# FEV-60_Motor_Driver_OnePhase.net
KiCad netlist of a schematic drawn in Altium Designer
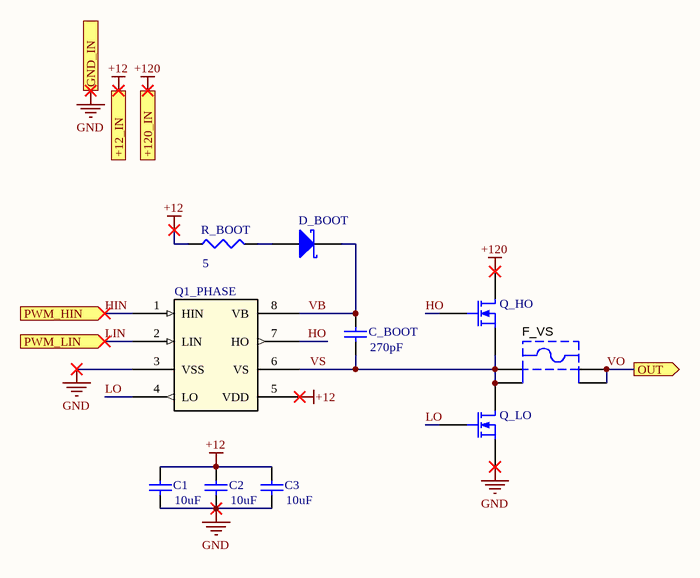
[diagram p0: FEV-60_Motor_Driver_OnePhase.SchDoc]

(export (version "E")
  (design (tool "Eeschema 10.0.6"))
  (components
    (comp (ref "C1")
      (value "10uF")
      (footprint "1608[0603]")
      (description "Capacitor (Semiconductor SIM Model)")
      (fields (field (name "Comment") "Cap Semi") (field (name "PUBLISHER") "Altium Limited"))
      (libsource (lib "Miscellaneous Devices") (part "Cap Semi"))
    )
    (comp (ref "C2")
      (value "10uF")
      (footprint "1608[0603]")
      (description "Capacitor (Semiconductor SIM Model)")
      (fields (field (name "Comment") "Cap Semi") (field (name "PUBLISHER") "Altium Limited"))
      (libsource (lib "Miscellaneous Devices") (part "Cap Semi"))
    )
    (comp (ref "C3")
      (value "10uF")
      (footprint "1608[0603]")
      (description "Capacitor (Semiconductor SIM Model)")
      (fields (field (name "Comment") "Cap Semi") (field (name "PUBLISHER") "Altium Limited"))
      (libsource (lib "Miscellaneous Devices") (part "Cap Semi"))
    )
    (comp (ref "C_BOOT")
      (value "270pF")
      (footprint "1608[0603]")
      (description "Capacitor (Semiconductor SIM Model)")
      (fields (field (name "Comment") "Cap Semi") (field (name "PUBLISHER") "Altium Limited"))
      (libsource (lib "Miscellaneous Devices") (part "Cap Semi"))
    )
    (comp (ref "D_BOOT")
      (value "STPS2200U")
      (footprint "SMB")
      (description "Schottky Diode")
      (fields (field (name "PUBLISHER") "Altium Limited"))
      (libsource (lib "Miscellaneous Devices") (part "D Schottky"))
    )
    (comp (ref "F_VS")
      (value "3568")
      (footprint "KSTN-3568_V")
      (description "Fuse Holder, 20 A, 500 V, -50 to 145 degC, 4-Pin THD, RoHS")
      (fields (field (name "MANUFACTURER") "Keystone"))
      (libsource (lib "FEV-60_Lib") (part "CMP-2000-05464-1"))
    )
    (comp (ref "Q1_PHASE")
      (value "FAN7191-F085")
      (footprint "SOIC8")
      (description "600 V / 4.5 A, High and Low\r\nSide Automotive Gate\r\nDriver IC")
      (fields (field (name "MANUFACTURER") "On Semiconductor"))
      (libsource (lib "FEV-60_Lib") (part "FAN7191-F085"))
    )
    (comp (ref "Q_HO")
      (value "TPH2900ENH")
      (footprint "TPH2900ENH")
      (description "N-Channel 200V 33A (Ta) 78W (Tc) Surface Mount 8-SOP Advance (5x5)")
      (fields (field (name "MANUFACTURER") "Toshiba") (field (name "PART NUMBER") "TPH2900ENHL1QCT-ND"))
      (libsource (lib "FEV-60_Lib") (part "TPH2900ENH"))
    )
    (comp (ref "Q_LO")
      (value "TPH2900ENH")
      (footprint "TPH2900ENH")
      (description "N-Channel 200V 33A (Ta) 78W (Tc) Surface Mount 8-SOP Advance (5x5)")
      (fields (field (name "MANUFACTURER") "Toshiba") (field (name "PART NUMBER") "TPH2900ENHL1QCT-ND"))
      (libsource (lib "FEV-60_Lib") (part "TPH2900ENH"))
    )
    (comp (ref "R_BOOT")
      (value "5")
      (footprint "J1-0603")
      (description "Resistor")
      (fields (field (name "Comment") "Res3") (field (name "PUBLISHER") "Altium Limited"))
      (libsource (lib "Miscellaneous Devices") (part "Res3"))
    )
  )
  (nets
    (net (code "1") (name "+12") (class "Default")
      (node (ref "C1") (pin "1") (pinfunction "1_1") (pintype "passive"))
      (node (ref "C2") (pin "1") (pinfunction "1_1") (pintype "passive"))
      (node (ref "C3") (pin "1") (pinfunction "1_1") (pintype "passive"))
      (node (ref "Q1_PHASE") (pin "5") (pinfunction "VDD_5") (pintype "power_in"))
      (node (ref "R_BOOT") (pin "1") (pinfunction "1_1") (pintype "passive"))
    )
    (net (code "2") (name "+120") (class "Default")
      (node (ref "Q_HO") (pin "1") (pinfunction "D_1") (pintype "passive"))
    )
    (net (code "3") (name "/HIN") (class "Default")
      (node (ref "Q1_PHASE") (pin "1") (pinfunction "HIN_1") (pintype "input+no_connect"))
    )
    (net (code "4") (name "/HO") (class "Default")
      (node (ref "Q1_PHASE") (pin "7") (pinfunction "HO_7") (pintype "output"))
      (node (ref "Q_HO") (pin "2") (pinfunction "G_2") (pintype "passive"))
    )
    (net (code "5") (name "/LIN") (class "Default")
      (node (ref "Q1_PHASE") (pin "2") (pinfunction "LIN_2") (pintype "input+no_connect"))
    )
    (net (code "6") (name "/LO") (class "Default")
      (node (ref "Q1_PHASE") (pin "4") (pinfunction "LO_4") (pintype "output"))
      (node (ref "Q_LO") (pin "2") (pinfunction "G_2") (pintype "passive"))
    )
    (net (code "7") (name "/VB") (class "Default")
      (node (ref "C_BOOT") (pin "2") (pinfunction "2_2") (pintype "passive"))
      (node (ref "D_BOOT") (pin "2") (pinfunction "K_2") (pintype "passive"))
      (node (ref "Q1_PHASE") (pin "8") (pinfunction "VB_8") (pintype "power_in"))
    )
    (net (code "8") (name "/VO") (class "Default")
      (node (ref "F_VS") (pin "3") (pinfunction "3_3") (pintype "passive"))
      (node (ref "F_VS") (pin "4") (pinfunction "4_4") (pintype "passive"))
    )
    (net (code "9") (name "/VS") (class "Default")
      (node (ref "C_BOOT") (pin "1") (pinfunction "1_1") (pintype "passive"))
      (node (ref "F_VS") (pin "1") (pinfunction "1_1") (pintype "passive"))
      (node (ref "F_VS") (pin "2") (pinfunction "2_2") (pintype "passive"))
      (node (ref "Q1_PHASE") (pin "6") (pinfunction "VS_6") (pintype "power_in"))
      (node (ref "Q_HO") (pin "3") (pinfunction "S_3") (pintype "passive"))
      (node (ref "Q_LO") (pin "1") (pinfunction "D_1") (pintype "passive"))
    )
    (net (code "10") (name "GND") (class "Default")
      (node (ref "C1") (pin "2") (pinfunction "2_2") (pintype "passive"))
      (node (ref "C2") (pin "2") (pinfunction "2_2") (pintype "passive"))
      (node (ref "C3") (pin "2") (pinfunction "2_2") (pintype "passive"))
      (node (ref "Q1_PHASE") (pin "3") (pinfunction "VSS_3") (pintype "power_in"))
      (node (ref "Q_LO") (pin "3") (pinfunction "S_3") (pintype "passive"))
    )
    (net (code "11") (name "Net-(D_BOOT-A)") (class "Default")
      (node (ref "D_BOOT") (pin "1") (pinfunction "A_1") (pintype "passive"))
      (node (ref "R_BOOT") (pin "2") (pinfunction "2_2") (pintype "passive"))
    )
  )
)
